# GCM_SCH.net
KiCad netlist of a schematic drawn in Altium Designer
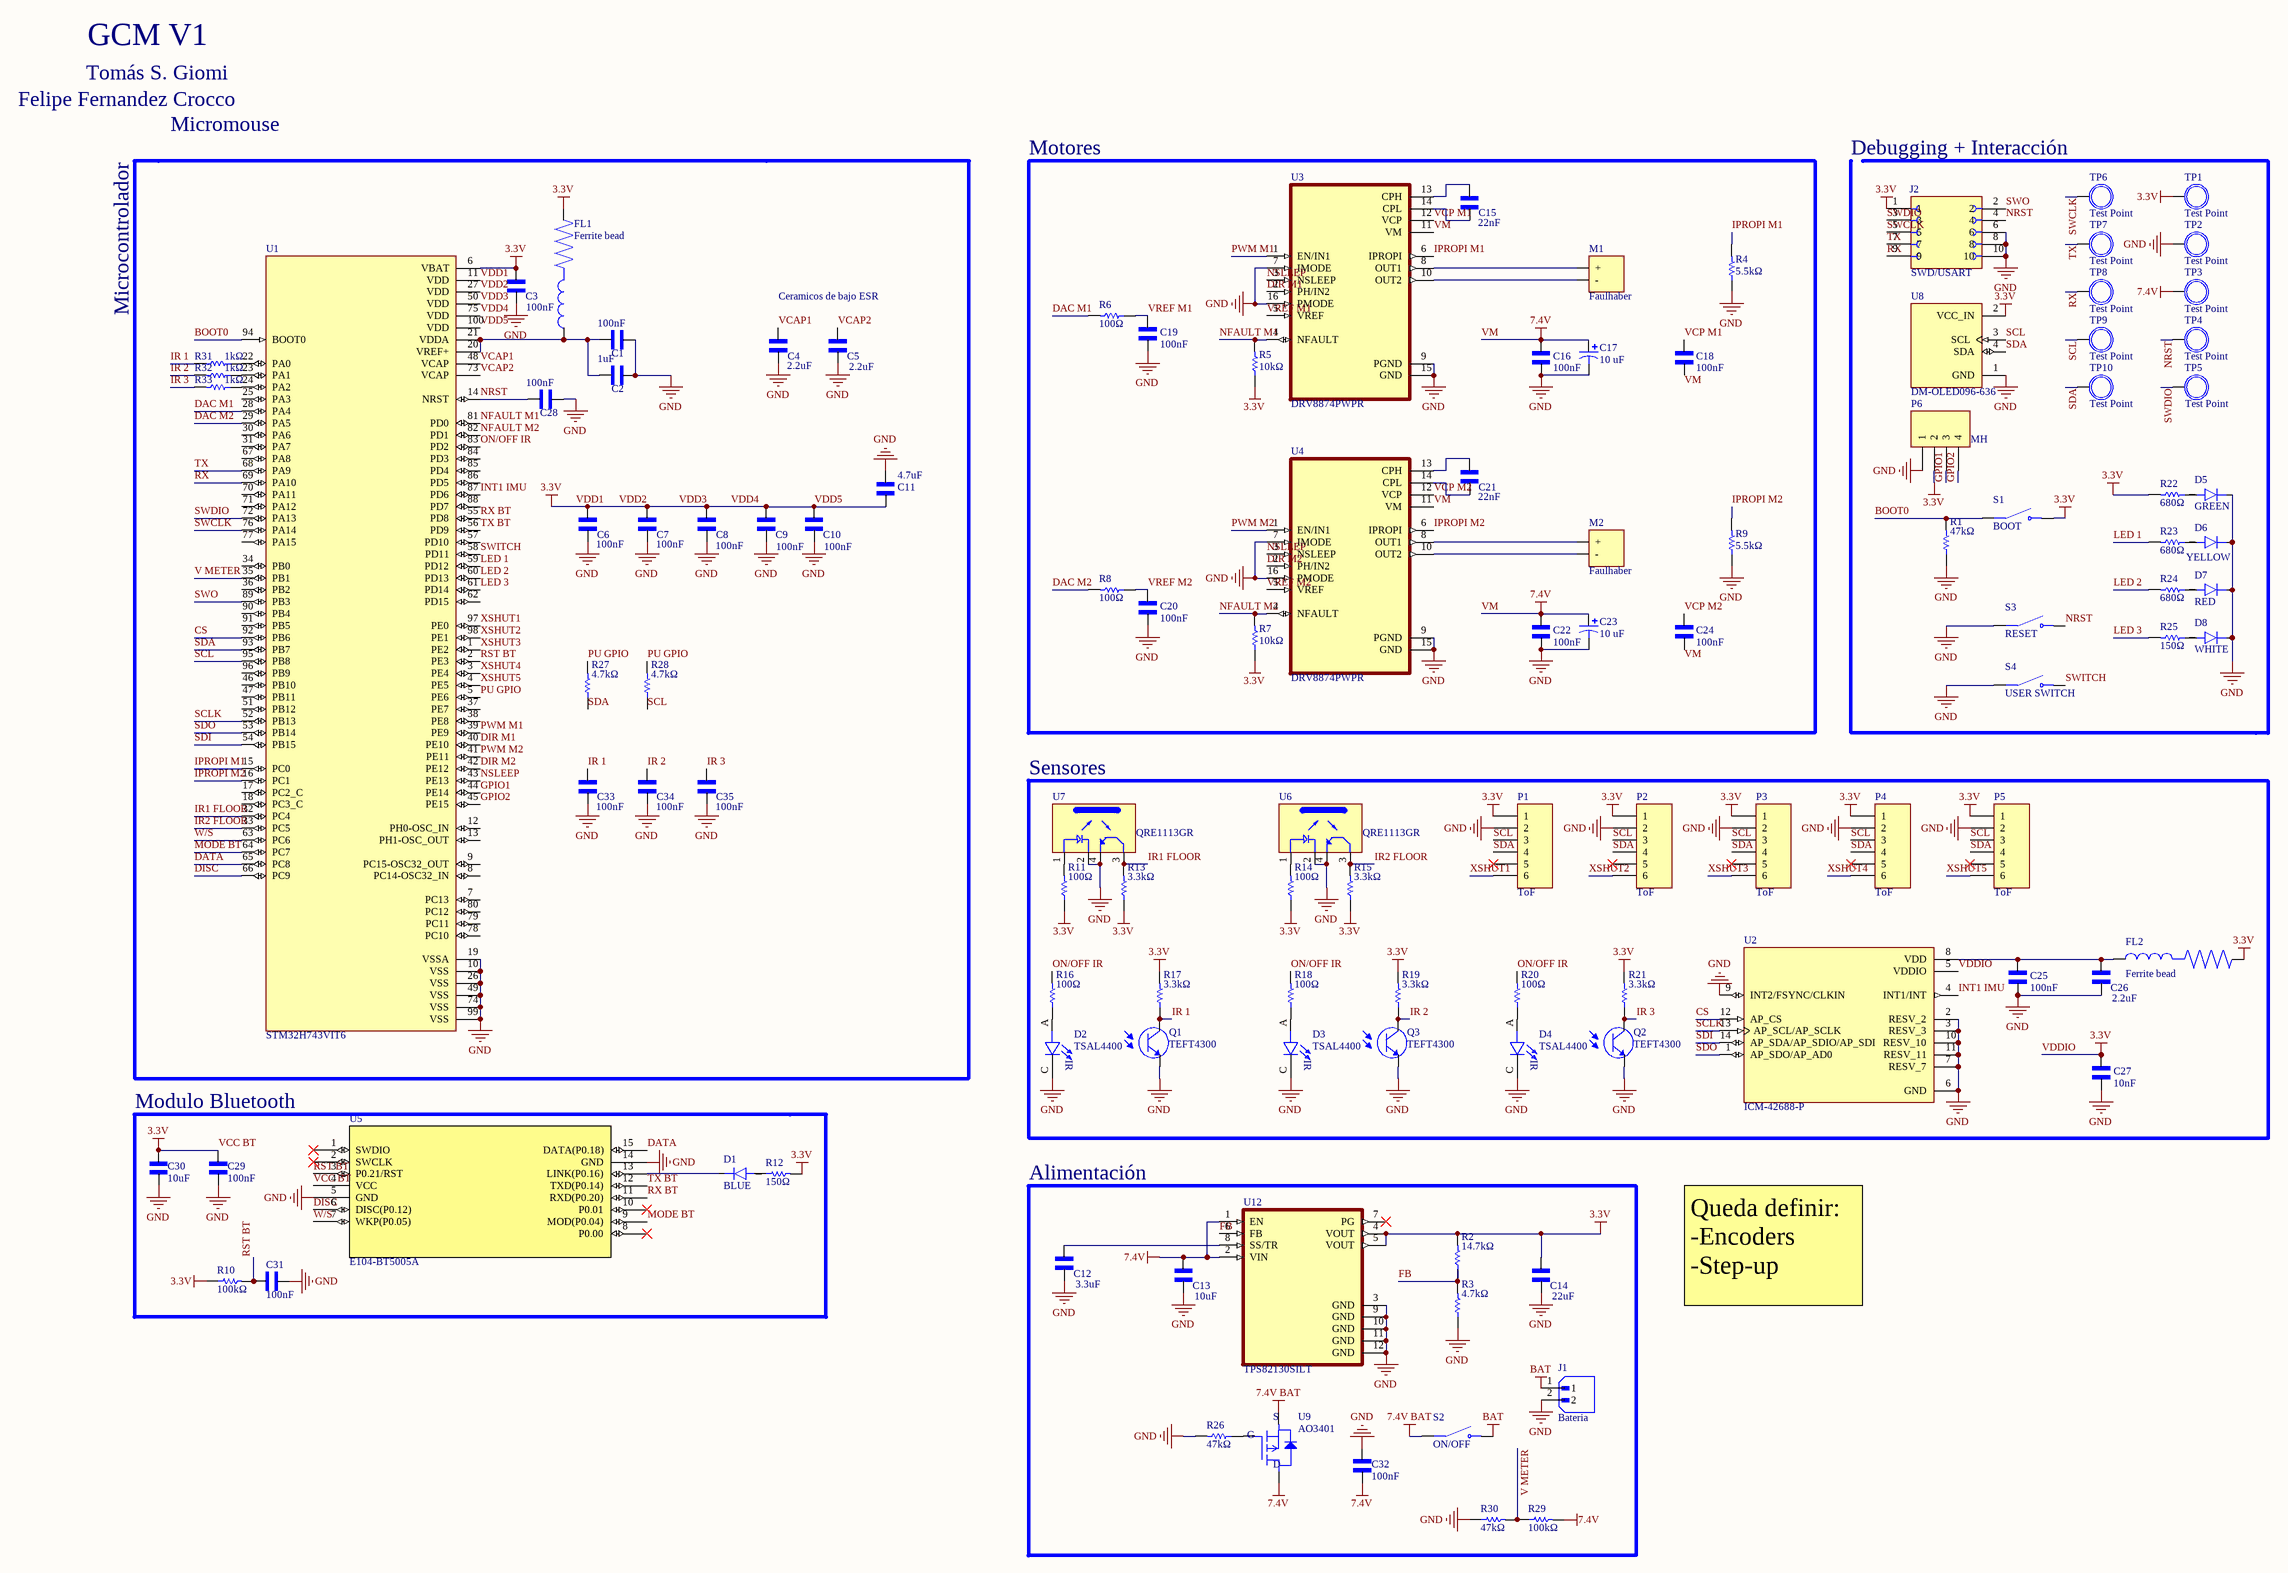
[diagram p0: GCM_SCH.SchDoc]

(export (version "E")
  (design (tool "Eeschema 10.0.6"))
  (components
    (comp (ref "C1")
      (value "100nF")
      (footprint "CAPACITOR TANTALIO")
      (description "0805")
      (fields (field (name "MP") "GRM035R60J475ME15D") (field (name "MF") "Murata"))
      (libsource (lib "") (part "CAPACITOR TANTALIO_1"))
    )
    (comp (ref "C2")
      (value "1uF")
      (footprint "CAPACITOR TANTALIO")
      (description "0805")
      (fields (field (name "MP") "GRM035R60J475ME15D") (field (name "MF") "Murata"))
      (libsource (lib "") (part "CAPACITOR TANTALIO_1"))
    )
    (comp (ref "C3")
      (value "100nF")
      (footprint "CAPACITOR TANTALIO")
      (description "0805")
      (fields (field (name "MP") "GRM035R60J475ME15D") (field (name "MF") "Murata"))
      (libsource (lib "GCMLibreriasSCH") (part "CAPACITOR TANTALIO"))
    )
    (comp (ref "C4")
      (value "2.2uF")
      (footprint "CAPACITOR TANTALIO")
      (description "0805")
      (fields (field (name "MP") "GRM035R60J475ME15D") (field (name "MF") "Murata"))
      (libsource (lib "GCMLibreriasSCH") (part "CAPACITOR TANTALIO"))
    )
    (comp (ref "C5")
      (value "2.2uF")
      (footprint "CAPACITOR TANTALIO")
      (description "0805")
      (fields (field (name "MP") "GRM035R60J475ME15D") (field (name "MF") "Murata"))
      (libsource (lib "GCMLibreriasSCH") (part "CAPACITOR TANTALIO"))
    )
    (comp (ref "C6")
      (value "100nF")
      (footprint "CAPACITOR TANTALIO")
      (description "0805")
      (fields (field (name "MP") "GRM035R60J475ME15D") (field (name "MF") "Murata"))
      (libsource (lib "GCMLibreriasSCH") (part "CAPACITOR TANTALIO"))
    )
    (comp (ref "C7")
      (value "100nF")
      (footprint "CAPACITOR TANTALIO")
      (description "0805")
      (fields (field (name "MP") "GRM035R60J475ME15D") (field (name "MF") "Murata"))
      (libsource (lib "GCMLibreriasSCH") (part "CAPACITOR TANTALIO"))
    )
    (comp (ref "C8")
      (value "100nF")
      (footprint "CAPACITOR TANTALIO")
      (description "0805")
      (fields (field (name "MP") "GRM035R60J475ME15D") (field (name "MF") "Murata"))
      (libsource (lib "GCMLibreriasSCH") (part "CAPACITOR TANTALIO"))
    )
    (comp (ref "C9")
      (value "100nF")
      (footprint "CAPACITOR TANTALIO")
      (description "0805")
      (fields (field (name "MP") "GRM035R60J475ME15D") (field (name "MF") "Murata"))
      (libsource (lib "GCMLibreriasSCH") (part "CAPACITOR TANTALIO"))
    )
    (comp (ref "C10")
      (value "100nF")
      (footprint "CAPACITOR TANTALIO")
      (description "0805")
      (fields (field (name "MP") "GRM035R60J475ME15D") (field (name "MF") "Murata"))
      (libsource (lib "GCMLibreriasSCH") (part "CAPACITOR TANTALIO"))
    )
    (comp (ref "C11")
      (value "4.7uF")
      (footprint "CAPACITOR TANTALIO")
      (description "0805")
      (fields (field (name "MP") "GRM035R60J475ME15D") (field (name "MF") "Murata"))
      (libsource (lib "GCMLibreriasSCH") (part "CAPACITOR TANTALIO"))
    )
    (comp (ref "C12")
      (value "3.3uF")
      (footprint "CAPACITOR TANTALIO")
      (description "0805")
      (fields (field (name "MP") "GRM035R60J475ME15D") (field (name "MF") "Murata"))
      (libsource (lib "GCMLibreriasSCH") (part "CAPACITOR TANTALIO"))
    )
    (comp (ref "C13")
      (value "10uF")
      (footprint "CAPACITOR TANTALIO")
      (description "0805")
      (fields (field (name "MP") "GRM035R60J475ME15D") (field (name "MF") "Murata"))
      (libsource (lib "GCMLibreriasSCH") (part "CAPACITOR TANTALIO"))
    )
    (comp (ref "C14")
      (value "22uF")
      (footprint "CAPACITOR TANTALIO")
      (description "0805")
      (fields (field (name "MP") "GRM035R60J475ME15D") (field (name "MF") "Murata"))
      (libsource (lib "GCMLibreriasSCH") (part "CAPACITOR TANTALIO"))
    )
    (comp (ref "C15")
      (value "22nF")
      (footprint "CAPACITOR TANTALIO")
      (description "0805")
      (fields (field (name "MP") "GRM035R60J475ME15D") (field (name "MF") "Murata"))
      (libsource (lib "GCMLibreriasSCH") (part "CAPACITOR TANTALIO"))
    )
    (comp (ref "C16")
      (value "100nF")
      (footprint "CAPACITOR TANTALIO")
      (description "0805")
      (fields (field (name "MP") "GRM035R60J475ME15D") (field (name "MF") "Murata"))
      (libsource (lib "GCMLibreriasSCH") (part "CAPACITOR TANTALIO"))
    )
    (comp (ref "C17")
      (value "10 uF")
      (footprint "Cap El 10uF")
      (libsource (lib "GCMLibreriasSCH") (part "Cap el 10 uF"))
    )
    (comp (ref "C18")
      (value "100nF")
      (footprint "CAPACITOR TANTALIO")
      (description "0805")
      (fields (field (name "MP") "GRM035R60J475ME15D") (field (name "MF") "Murata"))
      (libsource (lib "GCMLibreriasSCH") (part "CAPACITOR TANTALIO"))
    )
    (comp (ref "C19")
      (value "100nF")
      (footprint "CAPACITOR TANTALIO")
      (description "0805")
      (fields (field (name "MP") "GRM035R60J475ME15D") (field (name "MF") "Murata"))
      (libsource (lib "GCMLibreriasSCH") (part "CAPACITOR TANTALIO"))
    )
    (comp (ref "C20")
      (value "100nF")
      (footprint "CAPACITOR TANTALIO")
      (description "0805")
      (fields (field (name "MP") "GRM035R60J475ME15D") (field (name "MF") "Murata"))
      (libsource (lib "GCMLibreriasSCH") (part "CAPACITOR TANTALIO"))
    )
    (comp (ref "C21")
      (value "22nF")
      (footprint "CAPACITOR TANTALIO")
      (description "0805")
      (fields (field (name "MP") "GRM035R60J475ME15D") (field (name "MF") "Murata"))
      (libsource (lib "GCMLibreriasSCH") (part "CAPACITOR TANTALIO"))
    )
    (comp (ref "C22")
      (value "100nF")
      (footprint "CAPACITOR TANTALIO")
      (description "0805")
      (fields (field (name "MP") "GRM035R60J475ME15D") (field (name "MF") "Murata"))
      (libsource (lib "GCMLibreriasSCH") (part "CAPACITOR TANTALIO"))
    )
    (comp (ref "C23")
      (value "10 uF")
      (footprint "Cap El 10uF")
      (libsource (lib "GCMLibreriasSCH") (part "Cap el 10 uF"))
    )
    (comp (ref "C24")
      (value "100nF")
      (footprint "CAPACITOR TANTALIO")
      (description "0805")
      (fields (field (name "MP") "GRM035R60J475ME15D") (field (name "MF") "Murata"))
      (libsource (lib "GCMLibreriasSCH") (part "CAPACITOR TANTALIO"))
    )
    (comp (ref "C25")
      (value "100nF")
      (footprint "CAPACITOR TANTALIO")
      (description "0805")
      (fields (field (name "MP") "GRM035R60J475ME15D") (field (name "MF") "Murata"))
      (libsource (lib "GCMLibreriasSCH") (part "CAPACITOR TANTALIO"))
    )
    (comp (ref "C26")
      (value "2.2uF")
      (footprint "CAPACITOR TANTALIO")
      (description "0805")
      (fields (field (name "MP") "GRM035R60J475ME15D") (field (name "MF") "Murata"))
      (libsource (lib "GCMLibreriasSCH") (part "CAPACITOR TANTALIO"))
    )
    (comp (ref "C27")
      (value "10nF")
      (footprint "CAPACITOR TANTALIO")
      (description "0805")
      (fields (field (name "MP") "GRM035R60J475ME15D") (field (name "MF") "Murata"))
      (libsource (lib "GCMLibreriasSCH") (part "CAPACITOR TANTALIO"))
    )
    (comp (ref "C28")
      (value "100nF")
      (footprint "CAPACITOR TANTALIO")
      (description "0805")
      (fields (field (name "MP") "GRM035R60J475ME15D") (field (name "MF") "Murata"))
      (libsource (lib "") (part "CAPACITOR TANTALIO_1"))
    )
    (comp (ref "C29")
      (value "100nF")
      (footprint "CAPACITOR TANTALIO")
      (description "0805")
      (fields (field (name "MP") "GRM035R60J475ME15D") (field (name "MF") "Murata"))
      (libsource (lib "GCMLibreriasSCH") (part "CAPACITOR TANTALIO"))
    )
    (comp (ref "C30")
      (value "10uF")
      (footprint "CAPACITOR TANTALIO")
      (description "0805")
      (fields (field (name "MP") "GRM035R60J475ME15D") (field (name "MF") "Murata"))
      (libsource (lib "GCMLibreriasSCH") (part "CAPACITOR TANTALIO"))
    )
    (comp (ref "C31")
      (value "100nF")
      (footprint "CAPACITOR TANTALIO")
      (description "0805")
      (fields (field (name "MP") "GRM035R60J475ME15D") (field (name "MF") "Murata"))
      (libsource (lib "") (part "CAPACITOR TANTALIO_2"))
    )
    (comp (ref "C32")
      (value "100nF")
      (footprint "CAPACITOR TANTALIO")
      (description "0805")
      (fields (field (name "MP") "GRM035R60J475ME15D") (field (name "MF") "Murata"))
      (libsource (lib "") (part "CAPACITOR TANTALIO_3"))
    )
    (comp (ref "C33")
      (value "100nF")
      (footprint "CAPACITOR TANTALIO")
      (description "0805")
      (fields (field (name "MP") "GRM035R60J475ME15D") (field (name "MF") "Murata"))
      (libsource (lib "GCMLibreriasSCH") (part "CAPACITOR TANTALIO"))
    )
    (comp (ref "C34")
      (value "100nF")
      (footprint "CAPACITOR TANTALIO")
      (description "0805")
      (fields (field (name "MP") "GRM035R60J475ME15D") (field (name "MF") "Murata"))
      (libsource (lib "GCMLibreriasSCH") (part "CAPACITOR TANTALIO"))
    )
    (comp (ref "C35")
      (value "100nF")
      (footprint "CAPACITOR TANTALIO")
      (description "0805")
      (fields (field (name "MP") "GRM035R60J475ME15D") (field (name "MF") "Murata"))
      (libsource (lib "GCMLibreriasSCH") (part "CAPACITOR TANTALIO"))
    )
    (comp (ref "D1")
      (value "BLUE")
      (footprint "LED SMD")
      (description "0805")
      (fields (field (name "MP") "597-5311-402F"))
      (libsource (lib "GCMLibreriasSCH") (part "LED SMD"))
    )
    (comp (ref "D2")
      (value "TSAL4400")
      (footprint "GCMLibreriasPCB:LEDRD254W45D335H610")
      (description "Infrared Emitter 940nm 36mW/sr Circular Top Mount 2-Pin T-1 Bulk")
      (fields (field (name "MF") "Vishay Semiconductor"))
      (libsource (lib "GCMLibreriasSCH") (part "TSAL4400"))
    )
    (comp (ref "D3")
      (value "TSAL4400")
      (footprint "GCMLibreriasPCB:LEDRD254W45D335H610")
      (description "Infrared Emitter 940nm 36mW/sr Circular Top Mount 2-Pin T-1 Bulk")
      (fields (field (name "MF") "Vishay Semiconductor"))
      (libsource (lib "GCMLibreriasSCH") (part "TSAL4400"))
    )
    (comp (ref "D4")
      (value "TSAL4400")
      (footprint "GCMLibreriasPCB:LEDRD254W45D335H610")
      (description "Infrared Emitter 940nm 36mW/sr Circular Top Mount 2-Pin T-1 Bulk")
      (fields (field (name "MF") "Vishay Semiconductor"))
      (libsource (lib "GCMLibreriasSCH") (part "TSAL4400"))
    )
    (comp (ref "D5")
      (value "GREEN")
      (footprint "LED SMD")
      (description "0805")
      (fields (field (name "MP") "597-5311-402F"))
      (libsource (lib "GCMLibreriasSCH") (part "LED SMD"))
    )
    (comp (ref "D6")
      (value "YELLOW")
      (footprint "LED SMD")
      (description "0805")
      (fields (field (name "MP") "597-5311-402F"))
      (libsource (lib "GCMLibreriasSCH") (part "LED SMD"))
    )
    (comp (ref "D7")
      (value "RED")
      (footprint "LED SMD")
      (description "0805")
      (fields (field (name "MP") "597-5311-402F"))
      (libsource (lib "GCMLibreriasSCH") (part "LED SMD"))
    )
    (comp (ref "D8")
      (value "WHITE")
      (footprint "LED SMD")
      (description "0805")
      (fields (field (name "MP") "597-5311-402F"))
      (libsource (lib "GCMLibreriasSCH") (part "LED SMD"))
    )
    (comp (ref "FL1")
      (value "Ferrite bead")
      (footprint "BEADC1608X95N")
      (description "600 Ohms @ 100 MHz 1 - Ferrite Bead 0603 (1608 Metric) 500mA 380mOhm")
      (fields (field (name "MF") "Murata") (field (name "MP") "BLM18AG601SN1D"))
      (libsource (lib "GCMLibreriasSCH") (part "BLM18AG601SN1D"))
    )
    (comp (ref "FL2")
      (value "Ferrite bead")
      (footprint "BEADC1608X95N")
      (description "600 Ohms @ 100 MHz 1 - Ferrite Bead 0603 (1608 Metric) 500mA 380mOhm")
      (fields (field (name "MF") "Murata") (field (name "MP") "BLM18AG601SN1D"))
      (libsource (lib "GCMLibreriasSCH") (part "BLM18AG601SN1D"))
    )
    (comp (ref "J1")
      (value "Bateria")
      (footprint "JST_B2B-XH-A")
      (fields
        (field (name "MF") "{'manufacturer': u'JST Sales America Inc.'}")
        (field (name "MP") "B2B-XH-A")
      )
      (libsource (lib "GCMLibreriasSCH") (part "B2B-XH-A"))
    )
    (comp (ref "J2")
      (value "SWD/USART")
      (footprint "AMPHENOL_20021311-00026T4LF")
      (fields (field (name "MF") "Amphenol ICC") (field (name "MP") "20021311-00026T4LF"))
      (libsource (lib "GCMLibreriasSCH") (part "20021311-00026T4LF"))
    )
    (comp (ref "M1")
      (value "Faulhaber")
      (footprint "MOTOR")
      (fields (field (name "PUBLISHER") "Altium Limited"))
      (libsource (lib "GCMLibreriasSCH") (part "Faulhaber"))
    )
    (comp (ref "M2")
      (value "Faulhaber")
      (footprint "MOTOR")
      (fields (field (name "PUBLISHER") "Altium Limited"))
      (libsource (lib "GCMLibreriasSCH") (part "Faulhaber"))
    )
    (comp (ref "P1")
      (value "ToF")
      (footprint "FHDR1X6")
      (fields (field (name "PUBLISHER") "Altium Limited"))
      (libsource (lib "GCMLibreriasSCH") (part "FHeader 6X1"))
    )
    (comp (ref "P2")
      (value "ToF")
      (footprint "FHDR1X6")
      (fields (field (name "PUBLISHER") "Altium Limited"))
      (libsource (lib "GCMLibreriasSCH") (part "FHeader 6X1"))
    )
    (comp (ref "P3")
      (value "ToF")
      (footprint "FHDR1X6")
      (fields (field (name "PUBLISHER") "Altium Limited"))
      (libsource (lib "GCMLibreriasSCH") (part "FHeader 6X1"))
    )
    (comp (ref "P4")
      (value "ToF")
      (footprint "FHDR1X6")
      (fields (field (name "PUBLISHER") "Altium Limited"))
      (libsource (lib "GCMLibreriasSCH") (part "FHeader 6X1"))
    )
    (comp (ref "P5")
      (value "ToF")
      (footprint "FHDR1X6")
      (fields (field (name "PUBLISHER") "Altium Limited"))
      (libsource (lib "GCMLibreriasSCH") (part "FHeader 6X1"))
    )
    (comp (ref "P6")
      (value "MH")
      (footprint "FHDR1X4")
      (fields (field (name "PUBLISHER") "Altium Limited"))
      (libsource (lib "GCMLibreriasSCH") (part "FHeader 4X1_1"))
    )
    (comp (ref "Q1")
      (value "TEFT4300")
      (footprint "XDCR_TEFT4300")
      (description "Phototransistors 925nm Top View Radial, 3mm Dia (T-1)")
      (fields (field (name "MF") "Vishay Semiconductor"))
      (libsource (lib "GCMLibreriasSCH") (part "TEFT4300"))
    )
    (comp (ref "Q2")
      (value "TEFT4300")
      (footprint "XDCR_TEFT4300")
      (description "Phototransistors 925nm Top View Radial, 3mm Dia (T-1)")
      (fields (field (name "MF") "Vishay Semiconductor"))
      (libsource (lib "GCMLibreriasSCH") (part "TEFT4300"))
    )
    (comp (ref "Q3")
      (value "TEFT4300")
      (footprint "XDCR_TEFT4300")
      (description "Phototransistors 925nm Top View Radial, 3mm Dia (T-1)")
      (fields (field (name "MF") "Vishay Semiconductor"))
      (libsource (lib "GCMLibreriasSCH") (part "TEFT4300"))
    )
    (comp (ref "R1")
      (value "47kΩ")
      (footprint "RESISTENCIA SMD")
      (description "0805")
      (fields (field (name "PUBLISHER") "Altium Limited"))
      (libsource (lib "GCMLibreriasSCH") (part "RESISTENCIA"))
    )
    (comp (ref "R2")
      (value "14.7kΩ")
      (footprint "RESISTENCIA SMD")
      (description "0805")
      (fields (field (name "PUBLISHER") "Altium Limited"))
      (libsource (lib "GCMLibreriasSCH") (part "RESISTENCIA"))
    )
    (comp (ref "R3")
      (value "4.7kΩ")
      (footprint "RESISTENCIA SMD")
      (description "0805")
      (fields (field (name "PUBLISHER") "Altium Limited"))
      (libsource (lib "GCMLibreriasSCH") (part "RESISTENCIA"))
    )
    (comp (ref "R4")
      (value "5.5kΩ")
      (footprint "RESISTENCIA SMD")
      (description "0805")
      (fields (field (name "PUBLISHER") "Altium Limited"))
      (libsource (lib "GCMLibreriasSCH") (part "RESISTENCIA"))
    )
    (comp (ref "R5")
      (value "10kΩ")
      (footprint "RESISTENCIA SMD")
      (description "0805")
      (fields (field (name "PUBLISHER") "Altium Limited"))
      (libsource (lib "GCMLibreriasSCH") (part "RESISTENCIA"))
    )
    (comp (ref "R6")
      (value "100Ω")
      (footprint "RESISTENCIA SMD")
      (description "0805")
      (fields (field (name "PUBLISHER") "Altium Limited"))
      (libsource (lib "GCMLibreriasSCH") (part "RESISTENCIA"))
    )
    (comp (ref "R7")
      (value "10kΩ")
      (footprint "RESISTENCIA SMD")
      (description "0805")
      (fields (field (name "PUBLISHER") "Altium Limited"))
      (libsource (lib "GCMLibreriasSCH") (part "RESISTENCIA"))
    )
    (comp (ref "R8")
      (value "100Ω")
      (footprint "RESISTENCIA SMD")
      (description "0805")
      (fields (field (name "PUBLISHER") "Altium Limited"))
      (libsource (lib "GCMLibreriasSCH") (part "RESISTENCIA"))
    )
    (comp (ref "R9")
      (value "5.5kΩ")
      (footprint "RESISTENCIA SMD")
      (description "0805")
      (fields (field (name "PUBLISHER") "Altium Limited"))
      (libsource (lib "GCMLibreriasSCH") (part "RESISTENCIA"))
    )
    (comp (ref "R10")
      (value "100kΩ")
      (footprint "RESISTENCIA SMD")
      (description "0805")
      (fields (field (name "PUBLISHER") "Altium Limited"))
      (libsource (lib "GCMLibreriasSCH") (part "RESISTENCIA"))
    )
    (comp (ref "R11")
      (value "100Ω")
      (footprint "RESISTENCIA SMD")
      (description "0805")
      (fields (field (name "PUBLISHER") "Altium Limited"))
      (libsource (lib "GCMLibreriasSCH") (part "RESISTENCIA"))
    )
    (comp (ref "R12")
      (value "150Ω")
      (footprint "RESISTENCIA SMD")
      (description "0805")
      (fields (field (name "PUBLISHER") "Altium Limited"))
      (libsource (lib "GCMLibreriasSCH") (part "RESISTENCIA"))
    )
    (comp (ref "R13")
      (value "3.3kΩ")
      (footprint "RESISTENCIA SMD")
      (description "0805")
      (fields (field (name "PUBLISHER") "Altium Limited"))
      (libsource (lib "GCMLibreriasSCH") (part "RESISTENCIA"))
    )
    (comp (ref "R14")
      (value "100Ω")
      (footprint "RESISTENCIA SMD")
      (description "0805")
      (fields (field (name "PUBLISHER") "Altium Limited"))
      (libsource (lib "GCMLibreriasSCH") (part "RESISTENCIA"))
    )
    (comp (ref "R15")
      (value "3.3kΩ")
      (footprint "RESISTENCIA SMD")
      (description "0805")
      (fields (field (name "PUBLISHER") "Altium Limited"))
      (libsource (lib "GCMLibreriasSCH") (part "RESISTENCIA"))
    )
    (comp (ref "R16")
      (value "100Ω")
      (footprint "RESISTENCIA SMD")
      (description "0805")
      (fields (field (name "PUBLISHER") "Altium Limited"))
      (libsource (lib "GCMLibreriasSCH") (part "RESISTENCIA"))
    )
    (comp (ref "R17")
      (value "3.3kΩ")
      (footprint "RESISTENCIA SMD")
      (description "0805")
      (fields (field (name "PUBLISHER") "Altium Limited"))
      (libsource (lib "GCMLibreriasSCH") (part "RESISTENCIA"))
    )
    (comp (ref "R18")
      (value "100Ω")
      (footprint "RESISTENCIA SMD")
      (description "0805")
      (fields (field (name "PUBLISHER") "Altium Limited"))
      (libsource (lib "GCMLibreriasSCH") (part "RESISTENCIA"))
    )
    (comp (ref "R19")
      (value "3.3kΩ")
      (footprint "RESISTENCIA SMD")
      (description "0805")
      (fields (field (name "PUBLISHER") "Altium Limited"))
      (libsource (lib "GCMLibreriasSCH") (part "RESISTENCIA"))
    )
    (comp (ref "R20")
      (value "100Ω")
      (footprint "RESISTENCIA SMD")
      (description "0805")
      (fields (field (name "PUBLISHER") "Altium Limited"))
      (libsource (lib "GCMLibreriasSCH") (part "RESISTENCIA"))
    )
    (comp (ref "R21")
      (value "3.3kΩ")
      (footprint "RESISTENCIA SMD")
      (description "0805")
      (fields (field (name "PUBLISHER") "Altium Limited"))
      (libsource (lib "GCMLibreriasSCH") (part "RESISTENCIA"))
    )
    (comp (ref "R22")
      (value "680Ω")
      (footprint "RESISTENCIA SMD")
      (description "0805")
      (fields (field (name "PUBLISHER") "Altium Limited"))
      (libsource (lib "GCMLibreriasSCH") (part "RESISTENCIA"))
    )
    (comp (ref "R23")
      (value "680Ω")
      (footprint "RESISTENCIA SMD")
      (description "0805")
      (fields (field (name "PUBLISHER") "Altium Limited"))
      (libsource (lib "GCMLibreriasSCH") (part "RESISTENCIA"))
    )
    (comp (ref "R24")
      (value "680Ω")
      (footprint "RESISTENCIA SMD")
      (description "0805")
      (fields (field (name "PUBLISHER") "Altium Limited"))
      (libsource (lib "GCMLibreriasSCH") (part "RESISTENCIA"))
    )
    (comp (ref "R25")
      (value "150Ω")
      (footprint "RESISTENCIA SMD")
      (description "0805")
      (fields (field (name "PUBLISHER") "Altium Limited"))
      (libsource (lib "GCMLibreriasSCH") (part "RESISTENCIA"))
    )
    (comp (ref "R26")
      (value "47kΩ")
      (footprint "RESISTENCIA SMD")
      (description "0805")
      (fields (field (name "PUBLISHER") "Altium Limited"))
      (libsource (lib "GCMLibreriasSCH") (part "RESISTENCIA"))
    )
    (comp (ref "R27")
      (value "4.7kΩ")
      (footprint "RESISTENCIA SMD")
      (description "0805")
      (fields (field (name "PUBLISHER") "Altium Limited"))
      (libsource (lib "GCMLibreriasSCH") (part "RESISTENCIA"))
    )
    (comp (ref "R28")
      (value "4.7kΩ")
      (footprint "RESISTENCIA SMD")
      (description "0805")
      (fields (field (name "PUBLISHER") "Altium Limited"))
      (libsource (lib "GCMLibreriasSCH") (part "RESISTENCIA"))
    )
    (comp (ref "R29")
      (value "100kΩ")
      (footprint "RESISTENCIA SMD")
      (description "0805")
      (fields (field (name "PUBLISHER") "Altium Limited"))
      (libsource (lib "GCMLibreriasSCH") (part "RESISTENCIA"))
    )
    (comp (ref "R30")
      (value "47kΩ")
      (footprint "RESISTENCIA SMD")
      (description "0805")
      (fields (field (name "PUBLISHER") "Altium Limited"))
      (libsource (lib "GCMLibreriasSCH") (part "RESISTENCIA"))
    )
    (comp (ref "R31")
      (value "1kΩ")
      (footprint "RESISTENCIA SMD")
      (description "0805")
      (fields (field (name "PUBLISHER") "Altium Limited"))
      (libsource (lib "GCMLibreriasSCH") (part "RESISTENCIA"))
    )
    (comp (ref "R32")
      (value "1kΩ")
      (footprint "RESISTENCIA SMD")
      (description "0805")
      (fields (field (name "PUBLISHER") "Altium Limited"))
      (libsource (lib "GCMLibreriasSCH") (part "RESISTENCIA"))
    )
    (comp (ref "R33")
      (value "1kΩ")
      (footprint "RESISTENCIA SMD")
      (description "0805")
      (fields (field (name "PUBLISHER") "Altium Limited"))
      (libsource (lib "GCMLibreriasSCH") (part "RESISTENCIA"))
    )
    (comp (ref "S1")
      (value "BOOT")
      (footprint "SW_TS09-63-25-WT-160-SMT-TR")
      (description "6.1 x 3.7 mm, 2.5 mm Actuator Height, 160 gf, White, Surface Mount, SPST, Tactile Switch")
      (fields (field (name "MF") "Same Sky") (field (name "MP") "TS09-63-25-WT-160-SMT-TR"))
      (libsource (lib "GCMLibreriasSCH") (part "TS09-63-25-WT-160-SMT-TR"))
    )
    (comp (ref "S2")
      (value "ON/OFF")
      (footprint "SW_L101011ML04Q")
      (description "Switch Slide ON OFF SPST Side Slide 4A 250VAC 125VDC PC Pins Thru-Hole Bulk")
      (fields (field (name "MF") "C&K") (field (name "MP") "L101011ML04Q"))
      (libsource (lib "GCMLibreriasSCH") (part "L101011ML04Q"))
    )
    (comp (ref "S3")
      (value "RESET")
      (footprint "SW_TS09-63-25-WT-160-SMT-TR")
      (description "6.1 x 3.7 mm, 2.5 mm Actuator Height, 160 gf, White, Surface Mount, SPST, Tactile Switch")
      (fields (field (name "MF") "Same Sky") (field (name "MP") "TS09-63-25-WT-160-SMT-TR"))
      (libsource (lib "GCMLibreriasSCH") (part "TS09-63-25-WT-160-SMT-TR"))
    )
    (comp (ref "S4")
      (value "USER SWITCH")
      (footprint "SW_TS09-63-25-WT-160-SMT-TR")
      (description "6.1 x 3.7 mm, 2.5 mm Actuator Height, 160 gf, White, Surface Mount, SPST, Tactile Switch")
      (fields (field (name "MF") "Same Sky") (field (name "MP") "TS09-63-25-WT-160-SMT-TR"))
      (libsource (lib "GCMLibreriasSCH") (part "TS09-63-25-WT-160-SMT-TR"))
    )
    (comp (ref "TP1")
      (value "Test Point")
      (footprint "TestPoint")
      (libsource (lib "GCMLibreriasSCH") (part "Test Point"))
    )
    (comp (ref "TP2")
      (value "Test Point")
      (footprint "TestPoint")
      (libsource (lib "GCMLibreriasSCH") (part "Test Point"))
    )
    (comp (ref "TP3")
      (value "Test Point")
      (footprint "TestPoint")
      (libsource (lib "GCMLibreriasSCH") (part "Test Point"))
    )
    (comp (ref "TP4")
      (value "Test Point")
      (footprint "TestPoint")
      (libsource (lib "GCMLibreriasSCH") (part "Test Point"))
    )
    (comp (ref "TP5")
      (value "Test Point")
      (footprint "TestPoint")
      (libsource (lib "GCMLibreriasSCH") (part "Test Point"))
    )
    (comp (ref "TP6")
      (value "Test Point")
      (footprint "TestPoint")
      (libsource (lib "GCMLibreriasSCH") (part "Test Point"))
    )
    (comp (ref "TP7")
      (value "Test Point")
      (footprint "TestPoint")
      (libsource (lib "GCMLibreriasSCH") (part "Test Point"))
    )
    (comp (ref "TP8")
      (value "Test Point")
      (footprint "TestPoint")
      (libsource (lib "GCMLibreriasSCH") (part "Test Point"))
    )
    (comp (ref "TP9")
      (value "Test Point")
      (footprint "TestPoint")
      (libsource (lib "GCMLibreriasSCH") (part "Test Point"))
    )
    (comp (ref "TP10")
      (value "Test Point")
      (footprint "TestPoint")
      (libsource (lib "GCMLibreriasSCH") (part "Test Point"))
    )
    (comp (ref "U1")
      (value "STM32H743VIT6")
      (footprint "QFP50P1600X1600X160-100N")
      (fields (field (name "MF") "STMicroelectronics"))
      (libsource (lib "GCMLibreriasSCH") (part "STM32H743VIT6"))
    )
    (comp (ref "U2")
      (value "ICM-42688-P")
      (footprint "GCMLibreriasPCB:PQFN50P300X250X97-14N")
      (description "Accelerometer, Gyroscope, 6 Axis Sensor Output")
      (libsource (lib "GCMLibreriasSCH") (part "ICM-42688-P"))
    )
    (comp (ref "U3")
      (value "DRV8874PWPR")
      (footprint "SOP65P640X120-17N")
      (description "40-V, 6-A H-bridge motor driver with integrated current sensing feedback")
      (fields (field (name "MF") "Texas Instruments"))
      (libsource (lib "GCMLibreriasSCH") (part "DRV8874PWPR"))
    )
    (comp (ref "U4")
      (value "DRV8874PWPR")
      (footprint "SOP65P640X120-17N")
      (description "40-V, 6-A H-bridge motor driver with integrated current sensing feedback")
      (fields (field (name "MF") "Texas Instruments"))
      (libsource (lib "GCMLibreriasSCH") (part "DRV8874PWPR"))
    )
    (comp (ref "U5")
      (value "E104-BT5005A")
      (footprint "MOD15_E104-BT5005A_BYT")
      (description "No Description Available")
      (fields (field (name "COPYRIGHT") "Copyright (C) 2026 Ultra Librarian. All rights reserved."))
      (libsource (lib "GCMLibreriasSCH") (part "E104-BT5005A"))
    )
    (comp (ref "U6")
      (value "QRE1113GR")
      (footprint "SOIC180P460X187-4N")
      (description "Reflective Optical Sensor 0.039 (1mm) 4-SMD, Gull Wing")
      (fields (field (name "MF") "ON Semiconductor"))
      (libsource (lib "GCMLibreriasSCH") (part "QRE1113GR"))
    )
    (comp (ref "U7")
      (value "QRE1113GR")
      (footprint "SOIC180P460X187-4N")
      (description "Reflective Optical Sensor 0.039 (1mm) 4-SMD, Gull Wing")
      (fields (field (name "MF") "ON Semiconductor"))
      (libsource (lib "GCMLibreriasSCH") (part "QRE1113GR"))
    )
    (comp (ref "U8")
      (value "DM-OLED096-636")
      (footprint "MODULE_DM-OLED096-636")
      (description "0.96â€ 128 X 64 MONOCHROME GRAPHIC OLED DISPLAY MODULE - I2C")
      (fields (field (name "MF") "Display Module"))
      (libsource (lib "GCMLibreriasSCH") (part "DM-OLED096-636"))
    )
    (comp (ref "U9")
      (value "AO3401")
      (footprint "SOT23")
      (description "P-Channel 30 V 4A (Ta) 1.4W (Ta) Surface Mount SOT-23-3")
      (fields (field (name "MF") "Alpha & Omega Semiconductor"))
      (libsource (lib "GCMLibreriasSCH") (part "AO3401"))
    )
    (comp (ref "U12")
      (value "TPS82130SILT")
      (footprint "CONV_TPS82140SILR")
      (description "Non-Isolated PoL Module DC DC Converter 1 Output 0.9 ~ 5V - - - 3A 3V - 17V Input")
      (fields (field (name "MF") "Texas Instruments") (field (name "MP") "TPS82130SIL"))
      (libsource (lib "GCMLibreriasSCH") (part "TPS82130SILT"))
    )
  )
  (nets
    (net (code "1") (name "/BOOT0") (class "Default")
      (node (ref "R1") (pin "2") (pinfunction "2_2") (pintype "passive"))
      (node (ref "S1") (pin "1") (pinfunction "1_1") (pintype "passive"))
      (node (ref "U1") (pin "94") (pinfunction "BOOT0_94") (pintype "input"))
    )
    (net (code "2") (name "/CS") (class "Default")
      (node (ref "U1") (pin "92") (pinfunction "PB6_92") (pintype "bidirectional"))
      (node (ref "U2") (pin "12") (pinfunction "AP_CS_12") (pintype "input"))
    )
    (net (code "3") (name "/DAC M1") (class "Default")
      (node (ref "R6") (pin "2") (pinfunction "2_2") (pintype "passive"))
      (node (ref "U1") (pin "28") (pinfunction "PA4_28") (pintype "bidirectional"))
    )
    (net (code "4") (name "/DAC M2") (class "Default")
      (node (ref "R8") (pin "2") (pinfunction "2_2") (pintype "passive"))
      (node (ref "U1") (pin "29") (pinfunction "PA5_29") (pintype "bidirectional"))
    )
    (net (code "5") (name "/DATA") (class "Default")
      (node (ref "U1") (pin "65") (pinfunction "PC8_65") (pintype "bidirectional"))
      (node (ref "U5") (pin "15") (pinfunction "DATA(P0.18)_15") (pintype "bidirectional"))
    )
    (net (code "6") (name "/DIR M1") (class "Default")
      (node (ref "U1") (pin "40") (pinfunction "PE10_40") (pintype "bidirectional"))
      (node (ref "U3") (pin "2") (pinfunction "PH/IN2_2") (pintype "input"))
    )
    (net (code "7") (name "/DIR M2") (class "Default")
      (node (ref "U1") (pin "42") (pinfunction "PE12_42") (pintype "bidirectional"))
      (node (ref "U4") (pin "2") (pinfunction "PH/IN2_2") (pintype "input"))
    )
    (net (code "8") (name "/DISC") (class "Default")
      (node (ref "U1") (pin "66") (pinfunction "PC9_66") (pintype "bidirectional"))
      (node (ref "U5") (pin "6") (pinfunction "DISC(P0.12)_6") (pintype "bidirectional"))
    )
    (net (code "9") (name "/FB") (class "Default")
      (node (ref "R2") (pin "1") (pinfunction "1_1") (pintype "passive"))
      (node (ref "R3") (pin "2") (pinfunction "2_2") (pintype "passive"))
      (node (ref "U12") (pin "6") (pinfunction "FB_6") (pintype "input"))
    )
    (net (code "10") (name "/GPIO1") (class "Default")
      (node (ref "P6") (pin "3") (pinfunction "3_3") (pintype "passive"))
      (node (ref "U1") (pin "44") (pinfunction "PE14_44") (pintype "bidirectional"))
    )
    (net (code "11") (name "/GPIO2") (class "Default")
      (node (ref "P6") (pin "4") (pinfunction "4_4") (pintype "passive"))
      (node (ref "U1") (pin "45") (pinfunction "PE15_45") (pintype "bidirectional"))
    )
    (net (code "12") (name "/INT1 IMU") (class "Default")
      (node (ref "U1") (pin "87") (pinfunction "PD6_87") (pintype "bidirectional"))
      (node (ref "U2") (pin "4") (pinfunction "INT1/INT_4") (pintype "output"))
    )
    (net (code "13") (name "/IPROPI M1") (class "Default")
      (node (ref "R4") (pin "2") (pinfunction "2_2") (pintype "passive"))
      (node (ref "U1") (pin "15") (pinfunction "PC0_15") (pintype "bidirectional"))
      (node (ref "U3") (pin "6") (pinfunction "IPROPI_6") (pintype "output"))
    )
    (net (code "14") (name "/IPROPI M2") (class "Default")
      (node (ref "R9") (pin "2") (pinfunction "2_2") (pintype "passive"))
      (node (ref "U1") (pin "16") (pinfunction "PC1_16") (pintype "bidirectional"))
      (node (ref "U4") (pin "6") (pinfunction "IPROPI_6") (pintype "output"))
    )
    (net (code "15") (name "/IR 1") (class "Default")
      (node (ref "C33") (pin "2") (pinfunction "2_2") (pintype "passive"))
      (node (ref "Q1") (pin "C") (pinfunction "C_C") (pintype "passive"))
      (node (ref "R17") (pin "1") (pinfunction "1_1") (pintype "passive"))
      (node (ref "R31") (pin "2") (pinfunction "2_2") (pintype "passive"))
    )
    (net (code "16") (name "/IR 2") (class "Default")
      (node (ref "C34") (pin "2") (pinfunction "2_2") (pintype "passive"))
      (node (ref "Q3") (pin "C") (pinfunction "C_C") (pintype "passive"))
      (node (ref "R19") (pin "1") (pinfunction "1_1") (pintype "passive"))
      (node (ref "R32") (pin "2") (pinfunction "2_2") (pintype "passive"))
    )
    (net (code "17") (name "/IR 3") (class "Default")
      (node (ref "C35") (pin "2") (pinfunction "2_2") (pintype "passive"))
      (node (ref "Q2") (pin "C") (pinfunction "C_C") (pintype "passive"))
      (node (ref "R21") (pin "1") (pinfunction "1_1") (pintype "passive"))
      (node (ref "R33") (pin "2") (pinfunction "2_2") (pintype "passive"))
    )
    (net (code "18") (name "/IR1 FLOOR") (class "Default")
      (node (ref "R13") (pin "2") (pinfunction "2_2") (pintype "passive"))
      (node (ref "U1") (pin "32") (pinfunction "PC4_32") (pintype "bidirectional"))
      (node (ref "U7") (pin "3") (pinfunction "CT_3") (pintype "passive"))
    )
    (net (code "19") (name "/IR2 FLOOR") (class "Default")
      (node (ref "R15") (pin "2") (pinfunction "2_2") (pintype "passive"))
      (node (ref "U1") (pin "33") (pinfunction "PC5_33") (pintype "bidirectional"))
      (node (ref "U6") (pin "3") (pinfunction "CT_3") (pintype "passive"))
    )
    (net (code "20") (name "/LED 1") (class "Default")
      (node (ref "R23") (pin "2") (pinfunction "2_2") (pintype "passive"))
      (node (ref "U1") (pin "59") (pinfunction "PD12_59") (pintype "bidirectional"))
    )
    (net (code "21") (name "/LED 2") (class "Default")
      (node (ref "R24") (pin "2") (pinfunction "2_2") (pintype "passive"))
      (node (ref "U1") (pin "60") (pinfunction "PD13_60") (pintype "bidirectional"))
    )
    (net (code "22") (name "/LED 3") (class "Default")
      (node (ref "R25") (pin "2") (pinfunction "2_2") (pintype "passive"))
      (node (ref "U1") (pin "61") (pinfunction "PD14_61") (pintype "bidirectional"))
    )
    (net (code "23") (name "/MODE BT") (class "Default")
      (node (ref "U1") (pin "64") (pinfunction "PC7_64") (pintype "bidirectional"))
      (node (ref "U5") (pin "9") (pinfunction "MOD(P0.04)_9") (pintype "bidirectional"))
    )
    (net (code "24") (name "/NFAULT M1") (class "Default")
      (node (ref "R5") (pin "2") (pinfunction "2_2") (pintype "passive"))
      (node (ref "U1") (pin "81") (pinfunction "PD0_81") (pintype "bidirectional"))
      (node (ref "U3") (pin "4") (pinfunction "NFAULT_4") (pintype "bidirectional"))
    )
    (net (code "25") (name "/NFAULT M2") (class "Default")
      (node (ref "R7") (pin "2") (pinfunction "2_2") (pintype "passive"))
      (node (ref "U1") (pin "82") (pinfunction "PD1_82") (pintype "bidirectional"))
      (node (ref "U4") (pin "4") (pinfunction "NFAULT_4") (pintype "bidirectional"))
    )
    (net (code "26") (name "/NRST") (class "Default")
      (node (ref "C28") (pin "1") (pinfunction "1_1") (pintype "passive"))
      (node (ref "J2") (pin "4") (pinfunction "4_4") (pintype "passive"))
      (node (ref "S3") (pin "2") (pinfunction "2_2") (pintype "passive"))
      (node (ref "TP4") (pin "1") (pinfunction "1_1") (pintype "passive"))
      (node (ref "U1") (pin "14") (pinfunction "NRST_14") (pintype "bidirectional"))
    )
    (net (code "27") (name "/NSLEEP") (class "Default")
      (node (ref "U1") (pin "43") (pinfunction "PE13_43") (pintype "bidirectional"))
      (node (ref "U3") (pin "3") (pinfunction "NSLEEP_3") (pintype "input"))
      (node (ref "U4") (pin "3") (pinfunction "NSLEEP_3") (pintype "input"))
    )
    (net (code "28") (name "/ON{slash}OFF IR") (class "Default")
      (node (ref "R16") (pin "2") (pinfunction "2_2") (pintype "passive"))
      (node (ref "R18") (pin "2") (pinfunction "2_2") (pintype "passive"))
      (node (ref "R20") (pin "2") (pinfunction "2_2") (pintype "passive"))
      (node (ref "U1") (pin "83") (pinfunction "PD2_83") (pintype "bidirectional"))
    )
    (net (code "29") (name "/PU GPIO") (class "Default")
      (node (ref "R27") (pin "2") (pinfunction "2_2") (pintype "passive"))
      (node (ref "R28") (pin "2") (pinfunction "2_2") (pintype "passive"))
      (node (ref "U1") (pin "5") (pinfunction "PE6_5") (pintype "bidirectional"))
    )
    (net (code "30") (name "/PWM M1") (class "Default")
      (node (ref "U1") (pin "39") (pinfunction "PE9_39") (pintype "bidirectional"))
      (node (ref "U3") (pin "1") (pinfunction "EN/IN1_1") (pintype "input"))
    )
    (net (code "31") (name "/PWM M2") (class "Default")
      (node (ref "U1") (pin "41") (pinfunction "PE11_41") (pintype "bidirectional"))
      (node (ref "U4") (pin "1") (pinfunction "EN/IN1_1") (pintype "input"))
    )
    (net (code "32") (name "/RST BT") (class "Default")
      (node (ref "C31") (pin "2") (pinfunction "2_2") (pintype "passive"))
      (node (ref "R10") (pin "2") (pinfunction "2_2") (pintype "passive"))
      (node (ref "U1") (pin "2") (pinfunction "PE3_2") (pintype "bidirectional"))
      (node (ref "U5") (pin "3") (pinfunction "P0.21/RST_3") (pintype "bidirectional"))
    )
    (net (code "33") (name "/RX") (class "Default")
      (node (ref "J2") (pin "9") (pinfunction "9_9") (pintype "passive"))
      (node (ref "TP8") (pin "1") (pinfunction "1_1") (pintype "passive"))
      (node (ref "U1") (pin "69") (pinfunction "PA10_69") (pintype "bidirectional"))
    )
    (net (code "34") (name "/RX BT") (class "Default")
      (node (ref "U1") (pin "55") (pinfunction "PD8_55") (pintype "bidirectional"))
      (node (ref "U5") (pin "11") (pinfunction "RXD(P0.20)_11") (pintype "bidirectional"))
    )
    (net (code "35") (name "/SCL") (class "Default")
      (node (ref "P1") (pin "3") (pinfunction "3_3") (pintype "passive"))
      (node (ref "P2") (pin "3") (pinfunction "3_3") (pintype "passive"))
      (node (ref "P3") (pin "3") (pinfunction "3_3") (pintype "passive"))
      (node (ref "P4") (pin "3") (pinfunction "3_3") (pintype "passive"))
      (node (ref "P5") (pin "3") (pinfunction "3_3") (pintype "passive"))
      (node (ref "R28") (pin "1") (pinfunction "1_1") (pintype "passive"))
      (node (ref "TP9") (pin "1") (pinfunction "1_1") (pintype "passive"))
      (node (ref "U1") (pin "95") (pinfunction "PB8_95") (pintype "bidirectional"))
      (node (ref "U8") (pin "3") (pinfunction "SCL_3") (pintype "input"))
    )
    (net (code "36") (name "/SCLK") (class "Default")
      (node (ref "U1") (pin "52") (pinfunction "PB13_52") (pintype "bidirectional"))
      (node (ref "U2") (pin "13") (pinfunction "AP_SCL/AP_SCLK_13") (pintype "input"))
    )
    (net (code "37") (name "/SDA") (class "Default")
      (node (ref "P1") (pin "4") (pinfunction "4_4") (pintype "passive"))
      (node (ref "P2") (pin "4") (pinfunction "4_4") (pintype "passive"))
      (node (ref "P3") (pin "4") (pinfunction "4_4") (pintype "passive"))
      (node (ref "P4") (pin "4") (pinfunction "4_4") (pintype "passive"))
      (node (ref "P5") (pin "4") (pinfunction "4_4") (pintype "passive"))
      (node (ref "R27") (pin "1") (pinfunction "1_1") (pintype "passive"))
      (node (ref "TP10") (pin "1") (pinfunction "1_1") (pintype "passive"))
      (node (ref "U1") (pin "93") (pinfunction "PB7_93") (pintype "bidirectional"))
      (node (ref "U8") (pin "4") (pinfunction "SDA_4") (pintype "bidirectional"))
    )
    (net (code "38") (name "/SDI") (class "Default")
      (node (ref "U1") (pin "54") (pinfunction "PB15_54") (pintype "bidirectional"))
      (node (ref "U2") (pin "14") (pinfunction "AP_SDA/AP_SDIO/AP_SDI_14") (pintype "bidirectional"))
    )
    (net (code "39") (name "/SDO") (class "Default")
      (node (ref "U1") (pin "53") (pinfunction "PB14_53") (pintype "bidirectional"))
      (node (ref "U2") (pin "1") (pinfunction "AP_SDO/AP_AD0_1") (pintype "bidirectional"))
    )
    (net (code "40") (name "/SWCLK") (class "Default")
      (node (ref "J2") (pin "5") (pinfunction "5_5") (pintype "passive"))
      (node (ref "TP6") (pin "1") (pinfunction "1_1") (pintype "passive"))
      (node (ref "U1") (pin "76") (pinfunction "PA14_76") (pintype "bidirectional"))
    )
    (net (code "41") (name "/SWDIO") (class "Default")
      (node (ref "J2") (pin "3") (pinfunction "3_3") (pintype "passive"))
      (node (ref "TP5") (pin "1") (pinfunction "1_1") (pintype "passive"))
      (node (ref "U1") (pin "72") (pinfunction "PA13_72") (pintype "bidirectional"))
    )
    (net (code "42") (name "/SWITCH") (class "Default")
      (node (ref "S4") (pin "2") (pinfunction "2_2") (pintype "passive"))
      (node (ref "U1") (pin "58") (pinfunction "PD11_58") (pintype "bidirectional"))
    )
    (net (code "43") (name "/SWO") (class "Default")
      (node (ref "J2") (pin "2") (pinfunction "2_2") (pintype "passive"))
      (node (ref "U1") (pin "89") (pinfunction "PB3_89") (pintype "bidirectional"))
    )
    (net (code "44") (name "/TX") (class "Default")
      (node (ref "J2") (pin "7") (pinfunction "7_7") (pintype "passive"))
      (node (ref "TP7") (pin "1") (pinfunction "1_1") (pintype "passive"))
      (node (ref "U1") (pin "68") (pinfunction "PA9_68") (pintype "bidirectional"))
    )
    (net (code "45") (name "/TX BT") (class "Default")
      (node (ref "U1") (pin "56") (pinfunction "PD9_56") (pintype "bidirectional"))
      (node (ref "U5") (pin "12") (pinfunction "TXD(P0.14)_12") (pintype "bidirectional"))
    )
    (net (code "46") (name "/V METER") (class "Default")
      (node (ref "R29") (pin "1") (pinfunction "1_1") (pintype "passive"))
      (node (ref "R30") (pin "2") (pinfunction "2_2") (pintype "passive"))
      (node (ref "U1") (pin "35") (pinfunction "PB1_35") (pintype "bidirectional"))
    )
    (net (code "47") (name "/VCAP1") (class "Default")
      (node (ref "C4") (pin "2") (pinfunction "2_2") (pintype "passive"))
      (node (ref "U1") (pin "48") (pinfunction "VCAP_48") (pintype "power_in"))
    )
    (net (code "48") (name "/VCAP2") (class "Default")
      (node (ref "C5") (pin "2") (pinfunction "2_2") (pintype "passive"))
      (node (ref "U1") (pin "73") (pinfunction "VCAP_73") (pintype "power_in"))
    )
    (net (code "49") (name "/VCP M1") (class "Default")
      (node (ref "C18") (pin "2") (pinfunction "2_2") (pintype "passive"))
      (node (ref "U3") (pin "12") (pinfunction "VCP_12") (pintype "power_in"))
    )
    (net (code "50") (name "/VCP M2") (class "Default")
      (node (ref "C24") (pin "2") (pinfunction "2_2") (pintype "passive"))
      (node (ref "U4") (pin "12") (pinfunction "VCP_12") (pintype "power_in"))
    )
    (net (code "51") (name "/VREF M1") (class "Default")
      (node (ref "C19") (pin "2") (pinfunction "2_2") (pintype "passive"))
      (node (ref "R6") (pin "1") (pinfunction "1_1") (pintype "passive"))
      (node (ref "U3") (pin "5") (pinfunction "VREF_5") (pintype "input"))
    )
    (net (code "52") (name "/VREF M2") (class "Default")
      (node (ref "C20") (pin "2") (pinfunction "2_2") (pintype "passive"))
      (node (ref "R8") (pin "1") (pinfunction "1_1") (pintype "passive"))
      (node (ref "U4") (pin "5") (pinfunction "VREF_5") (pintype "input"))
    )
    (net (code "53") (name "/W{slash}S") (class "Default")
      (node (ref "U1") (pin "63") (pinfunction "PC6_63") (pintype "bidirectional"))
      (node (ref "U5") (pin "7") (pinfunction "WKP(P0.05)_7") (pintype "bidirectional"))
    )
    (net (code "54") (name "/XSHUT1") (class "Default")
      (node (ref "P1") (pin "6") (pinfunction "6_6") (pintype "passive"))
      (node (ref "U1") (pin "97") (pinfunction "PE0_97") (pintype "bidirectional"))
    )
    (net (code "55") (name "/XSHUT2") (class "Default")
      (node (ref "P2") (pin "6") (pinfunction "6_6") (pintype "passive"))
      (node (ref "U1") (pin "98") (pinfunction "PE1_98") (pintype "bidirectional"))
    )
    (net (code "56") (name "/XSHUT3") (class "Default")
      (node (ref "P3") (pin "6") (pinfunction "6_6") (pintype "passive"))
      (node (ref "U1") (pin "1") (pinfunction "PE2_1") (pintype "bidirectional"))
    )
    (net (code "57") (name "/XSHUT4") (class "Default")
      (node (ref "P4") (pin "6") (pinfunction "6_6") (pintype "passive"))
      (node (ref "U1") (pin "3") (pinfunction "PE4_3") (pintype "bidirectional"))
    )
    (net (code "58") (name "/XSHUT5") (class "Default")
      (node (ref "P5") (pin "6") (pinfunction "6_6") (pintype "passive"))
      (node (ref "U1") (pin "4") (pinfunction "PE5_4") (pintype "bidirectional"))
    )
    (net (code "59") (name "3.3V") (class "Default")
      (node (ref "C10") (pin "2") (pinfunction "2_2") (pintype "passive"))
      (node (ref "C11") (pin "1") (pinfunction "1_1") (pintype "passive"))
      (node (ref "C14") (pin "2") (pinfunction "2_2") (pintype "passive"))
      (node (ref "C27") (pin "2") (pinfunction "2_2") (pintype "passive"))
      (node (ref "C29") (pin "2") (pinfunction "2_2") (pintype "passive"))
      (node (ref "C3") (pin "2") (pinfunction "2_2") (pintype "passive"))
      (node (ref "C30") (pin "2") (pinfunction "2_2") (pintype "passive"))
      (node (ref "C6") (pin "2") (pinfunction "2_2") (pintype "passive"))
      (node (ref "C7") (pin "2") (pinfunction "2_2") (pintype "passive"))
      (node (ref "C8") (pin "2") (pinfunction "2_2") (pintype "passive"))
      (node (ref "C9") (pin "2") (pinfunction "2_2") (pintype "passive"))
      (node (ref "FL1") (pin "2") (pinfunction "2_2") (pintype "passive"))
      (node (ref "FL2") (pin "2") (pinfunction "2_2") (pintype "passive"))
      (node (ref "J2") (pin "1") (pinfunction "1_1") (pintype "passive"))
      (node (ref "P1") (pin "1") (pinfunction "1_1") (pintype "passive"))
      (node (ref "P2") (pin "1") (pinfunction "1_1") (pintype "passive"))
      (node (ref "P3") (pin "1") (pinfunction "1_1") (pintype "passive"))
      (node (ref "P4") (pin "1") (pinfunction "1_1") (pintype "passive"))
      (node (ref "P5") (pin "1") (pinfunction "1_1") (pintype "passive"))
      (node (ref "P6") (pin "2") (pinfunction "2_2") (pintype "passive"))
      (node (ref "R10") (pin "1") (pinfunction "1_1") (pintype "passive"))
      (node (ref "R11") (pin "1") (pinfunction "1_1") (pintype "passive"))
      (node (ref "R12") (pin "2") (pinfunction "2_2") (pintype "passive"))
      (node (ref "R13") (pin "1") (pinfunction "1_1") (pintype "passive"))
      (node (ref "R14") (pin "1") (pinfunction "1_1") (pintype "passive"))
      (node (ref "R15") (pin "1") (pinfunction "1_1") (pintype "passive"))
      (node (ref "R17") (pin "2") (pinfunction "2_2") (pintype "passive"))
      (node (ref "R19") (pin "2") (pinfunction "2_2") (pintype "passive"))
      (node (ref "R2") (pin "2") (pinfunction "2_2") (pintype "passive"))
      (node (ref "R21") (pin "2") (pinfunction "2_2") (pintype "passive"))
      (node (ref "R22") (pin "2") (pinfunction "2_2") (pintype "passive"))
      (node (ref "R5") (pin "1") (pinfunction "1_1") (pintype "passive"))
      (node (ref "R7") (pin "1") (pinfunction "1_1") (pintype "passive"))
      (node (ref "S1") (pin "2") (pinfunction "2_2") (pintype "passive"))
      (node (ref "TP1") (pin "1") (pinfunction "1_1") (pintype "passive"))
      (node (ref "U1") (pin "100") (pinfunction "VDD_100") (pintype "power_in"))
      (node (ref "U1") (pin "11") (pinfunction "VDD_11") (pintype "power_in"))
      (node (ref "U1") (pin "27") (pinfunction "VDD_27") (pintype "power_in"))
      (node (ref "U1") (pin "50") (pinfunction "VDD_50") (pintype "power_in"))
      (node (ref "U1") (pin "6") (pinfunction "VBAT_6") (pintype "power_in"))
      (node (ref "U1") (pin "75") (pinfunction "VDD_75") (pintype "power_in"))
      (node (ref "U12") (pin "4") (pinfunction "VOUT_4") (pintype "output"))
      (node (ref "U12") (pin "5") (pinfunction "VOUT_5") (pintype "output"))
      (node (ref "U2") (pin "5") (pinfunction "VDDIO_5") (pintype "power_in"))
      (node (ref "U5") (pin "4") (pinfunction "VCC_4") (pintype "power_in"))
      (node (ref "U8") (pin "2") (pinfunction "VCC_IN_2") (pintype "power_in"))
    )
    (net (code "60") (name "7.4V") (class "Default")
      (node (ref "C13") (pin "2") (pinfunction "2_2") (pintype "passive"))
      (node (ref "C16") (pin "2") (pinfunction "2_2") (pintype "passive"))
      (node (ref "C17") (pin "1") (pinfunction "1_1") (pintype "passive"))
      (node (ref "C22") (pin "2") (pinfunction "2_2") (pintype "passive"))
      (node (ref "C23") (pin "1") (pinfunction "1_1") (pintype "passive"))
      (node (ref "C32") (pin "2") (pinfunction "2_2") (pintype "passive"))
      (node (ref "R29") (pin "2") (pinfunction "2_2") (pintype "passive"))
      (node (ref "TP3") (pin "1") (pinfunction "1_1") (pintype "passive"))
      (node (ref "U12") (pin "1") (pinfunction "EN_1") (pintype "input"))
      (node (ref "U12") (pin "2") (pinfunction "VIN_2") (pintype "input"))
      (node (ref "U3") (pin "11") (pinfunction "VM_11") (pintype "power_in"))
      (node (ref "U4") (pin "11") (pinfunction "VM_11") (pintype "power_in"))
      (node (ref "U9") (pin "3") (pinfunction "D_3") (pintype "passive"))
    )
    (net (code "61") (name "7.4V BAT") (class "Default")
      (node (ref "S2") (pin "1") (pinfunction "COM_1") (pintype "passive"))
      (node (ref "U9") (pin "2") (pinfunction "S_2") (pintype "passive"))
    )
    (net (code "62") (name "BAT") (class "Default")
      (node (ref "J1") (pin "1") (pinfunction "1_1") (pintype "passive"))
      (node (ref "S2") (pin "2") (pinfunction "NO_2") (pintype "passive"))
    )
    (net (code "63") (name "GND") (class "Default")
      (node (ref "C1") (pin "2") (pinfunction "2_2") (pintype "passive"))
      (node (ref "C10") (pin "1") (pinfunction "1_1") (pintype "passive"))
      (node (ref "C11") (pin "2") (pinfunction "2_2") (pintype "passive"))
      (node (ref "C12") (pin "1") (pinfunction "1_1") (pintype "passive"))
      (node (ref "C13") (pin "1") (pinfunction "1_1") (pintype "passive"))
      (node (ref "C14") (pin "1") (pinfunction "1_1") (pintype "passive"))
      (node (ref "C16") (pin "1") (pinfunction "1_1") (pintype "passive"))
      (node (ref "C17") (pin "2") (pinfunction "2_2") (pintype "passive"))
      (node (ref "C19") (pin "1") (pinfunction "1_1") (pintype "passive"))
      (node (ref "C2") (pin "2") (pinfunction "2_2") (pintype "passive"))
      (node (ref "C20") (pin "1") (pinfunction "1_1") (pintype "passive"))
      (node (ref "C22") (pin "1") (pinfunction "1_1") (pintype "passive"))
      (node (ref "C23") (pin "2") (pinfunction "2_2") (pintype "passive"))
      (node (ref "C25") (pin "1") (pinfunction "1_1") (pintype "passive"))
      (node (ref "C26") (pin "1") (pinfunction "1_1") (pintype "passive"))
      (node (ref "C27") (pin "1") (pinfunction "1_1") (pintype "passive"))
      (node (ref "C28") (pin "2") (pinfunction "2_2") (pintype "passive"))
      (node (ref "C29") (pin "1") (pinfunction "1_1") (pintype "passive"))
      (node (ref "C3") (pin "1") (pinfunction "1_1") (pintype "passive"))
      (node (ref "C30") (pin "1") (pinfunction "1_1") (pintype "passive"))
      (node (ref "C31") (pin "1") (pinfunction "1_1") (pintype "passive"))
      (node (ref "C32") (pin "1") (pinfunction "1_1") (pintype "passive"))
      (node (ref "C33") (pin "1") (pinfunction "1_1") (pintype "passive"))
      (node (ref "C34") (pin "1") (pinfunction "1_1") (pintype "passive"))
      (node (ref "C35") (pin "1") (pinfunction "1_1") (pintype "passive"))
      (node (ref "C4") (pin "1") (pinfunction "1_1") (pintype "passive"))
      (node (ref "C5") (pin "1") (pinfunction "1_1") (pintype "passive"))
      (node (ref "C6") (pin "1") (pinfunction "1_1") (pintype "passive"))
      (node (ref "C7") (pin "1") (pinfunction "1_1") (pintype "passive"))
      (node (ref "C8") (pin "1") (pinfunction "1_1") (pintype "passive"))
      (node (ref "C9") (pin "1") (pinfunction "1_1") (pintype "passive"))
      (node (ref "D2") (pin "C") (pinfunction "C_C") (pintype "passive"))
      (node (ref "D3") (pin "C") (pinfunction "C_C") (pintype "passive"))
      (node (ref "D4") (pin "C") (pinfunction "C_C") (pintype "passive"))
      (node (ref "D5") (pin "C") (pinfunction "C_C") (pintype "passive"))
      (node (ref "D6") (pin "C") (pinfunction "C_C") (pintype "passive"))
      (node (ref "D7") (pin "C") (pinfunction "C_C") (pintype "passive"))
      (node (ref "D8") (pin "C") (pinfunction "C_C") (pintype "passive"))
      (node (ref "J1") (pin "2") (pinfunction "2_2") (pintype "passive"))
      (node (ref "J2") (pin "10") (pinfunction "10_10") (pintype "passive"))
      (node (ref "J2") (pin "6") (pinfunction "6_6") (pintype "passive"))
      (node (ref "J2") (pin "8") (pinfunction "8_8") (pintype "passive"))
      (node (ref "P1") (pin "2") (pinfunction "2_2") (pintype "passive"))
      (node (ref "P2") (pin "2") (pinfunction "2_2") (pintype "passive"))
      (node (ref "P3") (pin "2") (pinfunction "2_2") (pintype "passive"))
      (node (ref "P4") (pin "2") (pinfunction "2_2") (pintype "passive"))
      (node (ref "P5") (pin "2") (pinfunction "2_2") (pintype "passive"))
      (node (ref "P6") (pin "1") (pinfunction "1_1") (pintype "passive"))
      (node (ref "Q1") (pin "E") (pinfunction "E_E") (pintype "passive"))
      (node (ref "Q2") (pin "E") (pinfunction "E_E") (pintype "passive"))
      (node (ref "Q3") (pin "E") (pinfunction "E_E") (pintype "passive"))
      (node (ref "R1") (pin "1") (pinfunction "1_1") (pintype "passive"))
      (node (ref "R26") (pin "2") (pinfunction "2_2") (pintype "passive"))
      (node (ref "R3") (pin "1") (pinfunction "1_1") (pintype "passive"))
      (node (ref "R30") (pin "1") (pinfunction "1_1") (pintype "passive"))
      (node (ref "R4") (pin "1") (pinfunction "1_1") (pintype "passive"))
      (node (ref "R9") (pin "1") (pinfunction "1_1") (pintype "passive"))
      (node (ref "S3") (pin "1") (pinfunction "1_1") (pintype "passive"))
      (node (ref "S4") (pin "1") (pinfunction "1_1") (pintype "passive"))
      (node (ref "TP2") (pin "1") (pinfunction "1_1") (pintype "passive"))
      (node (ref "U1") (pin "10") (pinfunction "VSS_10") (pintype "power_in"))
      (node (ref "U1") (pin "19") (pinfunction "VSSA_19") (pintype "power_in"))
      (node (ref "U1") (pin "26") (pinfunction "VSS_26") (pintype "power_in"))
      (node (ref "U1") (pin "49") (pinfunction "VSS_49") (pintype "power_in"))
      (node (ref "U1") (pin "74") (pinfunction "VSS_74") (pintype "power_in"))
      (node (ref "U1") (pin "99") (pinfunction "VSS_99") (pintype "power_in"))
      (node (ref "U12") (pin "10") (pinfunction "GND_10") (pintype "power_in"))
      (node (ref "U12") (pin "11") (pinfunction "GND_11") (pintype "power_in"))
      (node (ref "U12") (pin "12") (pinfunction "GND_12") (pintype "power_in"))
      (node (ref "U12") (pin "3") (pinfunction "GND_3") (pintype "power_in"))
      (node (ref "U12") (pin "9") (pinfunction "GND_9") (pintype "power_in"))
      (node (ref "U2") (pin "10") (pinfunction "RESV_10_10") (pintype "passive"))
      (node (ref "U2") (pin "11") (pinfunction "RESV_11_11") (pintype "passive"))
      (node (ref "U2") (pin "2") (pinfunction "RESV_2_2") (pintype "passive"))
      (node (ref "U2") (pin "3") (pinfunction "RESV_3_3") (pintype "passive"))
      (node (ref "U2") (pin "6") (pinfunction "GND_6") (pintype "power_in"))
      (node (ref "U2") (pin "7") (pinfunction "RESV_7_7") (pintype "passive"))
      (node (ref "U2") (pin "9") (pinfunction "INT2/FSYNC/CLKIN_9") (pintype "bidirectional"))
      (node (ref "U3") (pin "15") (pinfunction "GND_15") (pintype "power_in"))
      (node (ref "U3") (pin "16") (pinfunction "PMODE_16") (pintype "input"))
      (node (ref "U3") (pin "7") (pinfunction "IMODE_7") (pintype "input"))
      (node (ref "U3") (pin "9") (pinfunction "PGND_9") (pintype "power_in"))
      (node (ref "U4") (pin "15") (pinfunction "GND_15") (pintype "power_in"))
      (node (ref "U4") (pin "16") (pinfunction "PMODE_16") (pintype "input"))
      (node (ref "U4") (pin "7") (pinfunction "IMODE_7") (pintype "input"))
      (node (ref "U4") (pin "9") (pinfunction "PGND_9") (pintype "power_in"))
      (node (ref "U5") (pin "14") (pinfunction "GND_14") (pintype "power_in"))
      (node (ref "U5") (pin "5") (pinfunction "GND_5") (pintype "power_in"))
      (node (ref "U6") (pin "2") (pinfunction "C_2") (pintype "passive"))
      (node (ref "U6") (pin "4") (pinfunction "ET_4") (pintype "passive"))
      (node (ref "U7") (pin "2") (pinfunction "C_2") (pintype "passive"))
      (node (ref "U7") (pin "4") (pinfunction "ET_4") (pintype "passive"))
      (node (ref "U8") (pin "1") (pinfunction "GND_1") (pintype "power_in"))
    )
    (net (code "64") (name "Net-(D2-PadA)") (class "Default")
      (node (ref "D2") (pin "A") (pinfunction "A_A") (pintype "passive"))
      (node (ref "R16") (pin "1") (pinfunction "1_1") (pintype "passive"))
    )
    (net (code "65") (name "Net-(D3-PadA)") (class "Default")
      (node (ref "D3") (pin "A") (pinfunction "A_A") (pintype "passive"))
      (node (ref "R18") (pin "1") (pinfunction "1_1") (pintype "passive"))
    )
    (net (code "66") (name "Net-(D4-PadA)") (class "Default")
      (node (ref "D4") (pin "A") (pinfunction "A_A") (pintype "passive"))
      (node (ref "R20") (pin "1") (pinfunction "1_1") (pintype "passive"))
    )
    (net (code "67") (name "Net-(M1-+)") (class "Default")
      (node (ref "M1") (pin "1") (pinfunction "+_1") (pintype "passive"))
      (node (ref "U3") (pin "8") (pinfunction "OUT1_8") (pintype "output"))
    )
    (net (code "68") (name "Net-(M1--)") (class "Default")
      (node (ref "M1") (pin "2") (pinfunction "-_2") (pintype "passive"))
      (node (ref "U3") (pin "10") (pinfunction "OUT2_10") (pintype "output"))
    )
    (net (code "69") (name "Net-(M2-+)") (class "Default")
      (node (ref "M2") (pin "1") (pinfunction "+_1") (pintype "passive"))
      (node (ref "U4") (pin "8") (pinfunction "OUT1_8") (pintype "output"))
    )
    (net (code "70") (name "Net-(M2--)") (class "Default")
      (node (ref "M2") (pin "2") (pinfunction "-_2") (pintype "passive"))
      (node (ref "U4") (pin "10") (pinfunction "OUT2_10") (pintype "output"))
    )
    (net (code "71") (name "Net-(U1-PA0)") (class "Default")
      (node (ref "R31") (pin "1") (pinfunction "1_1") (pintype "passive"))
      (node (ref "U1") (pin "22") (pinfunction "PA0_22") (pintype "bidirectional"))
    )
    (net (code "72") (name "Net-(U1-PA1)") (class "Default")
      (node (ref "R32") (pin "1") (pinfunction "1_1") (pintype "passive"))
      (node (ref "U1") (pin "23") (pinfunction "PA1_23") (pintype "bidirectional"))
    )
    (net (code "73") (name "Net-(U1-PA2)") (class "Default")
      (node (ref "R33") (pin "1") (pinfunction "1_1") (pintype "passive"))
      (node (ref "U1") (pin "24") (pinfunction "PA2_24") (pintype "bidirectional"))
    )
    (net (code "74") (name "Net-(U1-VDDA)") (class "Default")
      (node (ref "C1") (pin "1") (pinfunction "1_1") (pintype "passive"))
      (node (ref "C2") (pin "1") (pinfunction "1_1") (pintype "passive"))
      (node (ref "FL1") (pin "1") (pinfunction "1_1") (pintype "passive"))
      (node (ref "U1") (pin "20") (pinfunction "VREF+_20") (pintype "power_in"))
      (node (ref "U1") (pin "21") (pinfunction "VDDA_21") (pintype "power_in"))
    )
    (net (code "75") (name "Net-(U2-VDD)") (class "Default")
      (node (ref "C25") (pin "2") (pinfunction "2_2") (pintype "passive"))
      (node (ref "C26") (pin "2") (pinfunction "2_2") (pintype "passive"))
      (node (ref "FL2") (pin "1") (pinfunction "1_1") (pintype "passive"))
      (node (ref "U2") (pin "8") (pinfunction "VDD_8") (pintype "power_in"))
    )
    (net (code "76") (name "Net-(U3-CPH)") (class "Default")
      (node (ref "C15") (pin "2") (pinfunction "2_2") (pintype "passive"))
      (node (ref "U3") (pin "13") (pinfunction "CPH_13") (pintype "power_in"))
    )
    (net (code "77") (name "Net-(U3-CPL)") (class "Default")
      (node (ref "C15") (pin "1") (pinfunction "1_1") (pintype "passive"))
      (node (ref "U3") (pin "14") (pinfunction "CPL_14") (pintype "power_in"))
    )
    (net (code "78") (name "Net-(U4-CPH)") (class "Default")
      (node (ref "C21") (pin "2") (pinfunction "2_2") (pintype "passive"))
      (node (ref "U4") (pin "13") (pinfunction "CPH_13") (pintype "power_in"))
    )
    (net (code "79") (name "Net-(U4-CPL)") (class "Default")
      (node (ref "C21") (pin "1") (pinfunction "1_1") (pintype "passive"))
      (node (ref "U4") (pin "14") (pinfunction "CPL_14") (pintype "power_in"))
    )
    (net (code "80") (name "Net-(U5-LINK(P0.16))") (class "Default")
      (node (ref "D1") (pin "C") (pinfunction "C_C") (pintype "passive"))
      (node (ref "U5") (pin "13") (pinfunction "LINK(P0.16)_13") (pintype "bidirectional"))
    )
    (net (code "81") (name "Net-(U6-A)") (class "Default")
      (node (ref "R14") (pin "2") (pinfunction "2_2") (pintype "passive"))
      (node (ref "U6") (pin "1") (pinfunction "A_1") (pintype "passive"))
    )
    (net (code "82") (name "Net-(U7-A)") (class "Default")
      (node (ref "R11") (pin "2") (pinfunction "2_2") (pintype "passive"))
      (node (ref "U7") (pin "1") (pinfunction "A_1") (pintype "passive"))
    )
    (net (code "83") (name "Net-(U9-G)") (class "Default")
      (node (ref "R26") (pin "1") (pinfunction "1_1") (pintype "passive"))
      (node (ref "U9") (pin "1") (pinfunction "G_1") (pintype "passive"))
    )
    (net (code "84") (name "Net-(U12-SS{slash}TR)") (class "Default")
      (node (ref "C12") (pin "2") (pinfunction "2_2") (pintype "passive"))
      (node (ref "U12") (pin "8") (pinfunction "SS/TR_8") (pintype "input"))
    )
    (net (code "85") (name "unconnected-(C18-Pad1)") (class "Default")
      (node (ref "C18") (pin "1") (pinfunction "1_1") (pintype "passive"))
    )
    (net (code "86") (name "unconnected-(C24-Pad1)") (class "Default")
      (node (ref "C24") (pin "1") (pinfunction "1_1") (pintype "passive"))
    )
    (net (code "87") (name "unconnected-(D1-PadA)") (class "Default")
      (node (ref "D1") (pin "A") (pinfunction "A_A") (pintype "passive"))
    )
    (net (code "88") (name "unconnected-(D5-PadA)") (class "Default")
      (node (ref "D5") (pin "A") (pinfunction "A_A") (pintype "passive"))
    )
    (net (code "89") (name "unconnected-(D6-PadA)") (class "Default")
      (node (ref "D6") (pin "A") (pinfunction "A_A") (pintype "passive"))
    )
    (net (code "90") (name "unconnected-(D7-PadA)") (class "Default")
      (node (ref "D7") (pin "A") (pinfunction "A_A") (pintype "passive"))
    )
    (net (code "91") (name "unconnected-(D8-PadA)") (class "Default")
      (node (ref "D8") (pin "A") (pinfunction "A_A") (pintype "passive"))
    )
    (net (code "92") (name "unconnected-(P1-Pad5)") (class "Default")
      (node (ref "P1") (pin "5") (pinfunction "5_5") (pintype "passive+no_connect"))
    )
    (net (code "93") (name "unconnected-(P2-Pad5)") (class "Default")
      (node (ref "P2") (pin "5") (pinfunction "5_5") (pintype "passive+no_connect"))
    )
    (net (code "94") (name "unconnected-(P3-Pad5)") (class "Default")
      (node (ref "P3") (pin "5") (pinfunction "5_5") (pintype "passive+no_connect"))
    )
    (net (code "95") (name "unconnected-(P4-Pad5)") (class "Default")
      (node (ref "P4") (pin "5") (pinfunction "5_5") (pintype "passive+no_connect"))
    )
    (net (code "96") (name "unconnected-(P5-Pad5)") (class "Default")
      (node (ref "P5") (pin "5") (pinfunction "5_5") (pintype "passive+no_connect"))
    )
    (net (code "97") (name "unconnected-(R12-Pad1)") (class "Default")
      (node (ref "R12") (pin "1") (pinfunction "1_1") (pintype "passive"))
    )
    (net (code "98") (name "unconnected-(R22-Pad1)") (class "Default")
      (node (ref "R22") (pin "1") (pinfunction "1_1") (pintype "passive"))
    )
    (net (code "99") (name "unconnected-(R23-Pad1)") (class "Default")
      (node (ref "R23") (pin "1") (pinfunction "1_1") (pintype "passive"))
    )
    (net (code "100") (name "unconnected-(R24-Pad1)") (class "Default")
      (node (ref "R24") (pin "1") (pinfunction "1_1") (pintype "passive"))
    )
    (net (code "101") (name "unconnected-(R25-Pad1)") (class "Default")
      (node (ref "R25") (pin "1") (pinfunction "1_1") (pintype "passive"))
    )
    (net (code "102") (name "unconnected-(U1-PA3-Pad25)") (class "Default")
      (node (ref "U1") (pin "25") (pinfunction "PA3_25") (pintype "bidirectional"))
    )
    (net (code "103") (name "unconnected-(U1-PA6-Pad30)") (class "Default")
      (node (ref "U1") (pin "30") (pinfunction "PA6_30") (pintype "bidirectional"))
    )
    (net (code "104") (name "unconnected-(U1-PA7-Pad31)") (class "Default")
      (node (ref "U1") (pin "31") (pinfunction "PA7_31") (pintype "bidirectional"))
    )
    (net (code "105") (name "unconnected-(U1-PA8-Pad67)") (class "Default")
      (node (ref "U1") (pin "67") (pinfunction "PA8_67") (pintype "bidirectional"))
    )
    (net (code "106") (name "unconnected-(U1-PA11-Pad70)") (class "Default")
      (node (ref "U1") (pin "70") (pinfunction "PA11_70") (pintype "bidirectional"))
    )
    (net (code "107") (name "unconnected-(U1-PA12-Pad71)") (class "Default")
      (node (ref "U1") (pin "71") (pinfunction "PA12_71") (pintype "bidirectional"))
    )
    (net (code "108") (name "unconnected-(U1-PA15-Pad77)") (class "Default")
      (node (ref "U1") (pin "77") (pinfunction "PA15_77") (pintype "bidirectional"))
    )
    (net (code "109") (name "unconnected-(U1-PB0-Pad34)") (class "Default")
      (node (ref "U1") (pin "34") (pinfunction "PB0_34") (pintype "bidirectional"))
    )
    (net (code "110") (name "unconnected-(U1-PB2-Pad36)") (class "Default")
      (node (ref "U1") (pin "36") (pinfunction "PB2_36") (pintype "bidirectional"))
    )
    (net (code "111") (name "unconnected-(U1-PB4-Pad90)") (class "Default")
      (node (ref "U1") (pin "90") (pinfunction "PB4_90") (pintype "bidirectional"))
    )
    (net (code "112") (name "unconnected-(U1-PB5-Pad91)") (class "Default")
      (node (ref "U1") (pin "91") (pinfunction "PB5_91") (pintype "bidirectional"))
    )
    (net (code "113") (name "unconnected-(U1-PB9-Pad96)") (class "Default")
      (node (ref "U1") (pin "96") (pinfunction "PB9_96") (pintype "bidirectional"))
    )
    (net (code "114") (name "unconnected-(U1-PB10-Pad46)") (class "Default")
      (node (ref "U1") (pin "46") (pinfunction "PB10_46") (pintype "bidirectional"))
    )
    (net (code "115") (name "unconnected-(U1-PB11-Pad47)") (class "Default")
      (node (ref "U1") (pin "47") (pinfunction "PB11_47") (pintype "bidirectional"))
    )
    (net (code "116") (name "unconnected-(U1-PB12-Pad51)") (class "Default")
      (node (ref "U1") (pin "51") (pinfunction "PB12_51") (pintype "bidirectional"))
    )
    (net (code "117") (name "unconnected-(U1-PC2_C-Pad17)") (class "Default")
      (node (ref "U1") (pin "17") (pinfunction "PC2_C_17") (pintype "bidirectional"))
    )
    (net (code "118") (name "unconnected-(U1-PC3_C-Pad18)") (class "Default")
      (node (ref "U1") (pin "18") (pinfunction "PC3_C_18") (pintype "bidirectional"))
    )
    (net (code "119") (name "unconnected-(U1-PC10-Pad78)") (class "Default")
      (node (ref "U1") (pin "78") (pinfunction "PC10_78") (pintype "bidirectional"))
    )
    (net (code "120") (name "unconnected-(U1-PC11-Pad79)") (class "Default")
      (node (ref "U1") (pin "79") (pinfunction "PC11_79") (pintype "bidirectional"))
    )
    (net (code "121") (name "unconnected-(U1-PC12-Pad80)") (class "Default")
      (node (ref "U1") (pin "80") (pinfunction "PC12_80") (pintype "bidirectional"))
    )
    (net (code "122") (name "unconnected-(U1-PC13-Pad7)") (class "Default")
      (node (ref "U1") (pin "7") (pinfunction "PC13_7") (pintype "bidirectional"))
    )
    (net (code "123") (name "unconnected-(U1-PC14-OSC32_IN-Pad8)") (class "Default")
      (node (ref "U1") (pin "8") (pinfunction "PC14-OSC32_IN_8") (pintype "bidirectional"))
    )
    (net (code "124") (name "unconnected-(U1-PC15-OSC32_OUT-Pad9)") (class "Default")
      (node (ref "U1") (pin "9") (pinfunction "PC15-OSC32_OUT_9") (pintype "bidirectional"))
    )
    (net (code "125") (name "unconnected-(U1-PD3-Pad84)") (class "Default")
      (node (ref "U1") (pin "84") (pinfunction "PD3_84") (pintype "bidirectional"))
    )
    (net (code "126") (name "unconnected-(U1-PD4-Pad85)") (class "Default")
      (node (ref "U1") (pin "85") (pinfunction "PD4_85") (pintype "bidirectional"))
    )
    (net (code "127") (name "unconnected-(U1-PD5-Pad86)") (class "Default")
      (node (ref "U1") (pin "86") (pinfunction "PD5_86") (pintype "bidirectional"))
    )
    (net (code "128") (name "unconnected-(U1-PD7-Pad88)") (class "Default")
      (node (ref "U1") (pin "88") (pinfunction "PD7_88") (pintype "bidirectional"))
    )
    (net (code "129") (name "unconnected-(U1-PD10-Pad57)") (class "Default")
      (node (ref "U1") (pin "57") (pinfunction "PD10_57") (pintype "bidirectional"))
    )
    (net (code "130") (name "unconnected-(U1-PD15-Pad62)") (class "Default")
      (node (ref "U1") (pin "62") (pinfunction "PD15_62") (pintype "bidirectional"))
    )
    (net (code "131") (name "unconnected-(U1-PE7-Pad37)") (class "Default")
      (node (ref "U1") (pin "37") (pinfunction "PE7_37") (pintype "bidirectional"))
    )
    (net (code "132") (name "unconnected-(U1-PE8-Pad38)") (class "Default")
      (node (ref "U1") (pin "38") (pinfunction "PE8_38") (pintype "bidirectional"))
    )
    (net (code "133") (name "unconnected-(U1-PH0-OSC_IN-Pad12)") (class "Default")
      (node (ref "U1") (pin "12") (pinfunction "PH0-OSC_IN_12") (pintype "bidirectional"))
    )
    (net (code "134") (name "unconnected-(U1-PH1-OSC_OUT-Pad13)") (class "Default")
      (node (ref "U1") (pin "13") (pinfunction "PH1-OSC_OUT_13") (pintype "bidirectional"))
    )
    (net (code "135") (name "unconnected-(U5-P0.00-Pad8)") (class "Default")
      (node (ref "U5") (pin "8") (pinfunction "P0.00_8") (pintype "bidirectional+no_connect"))
    )
    (net (code "136") (name "unconnected-(U5-P0.01-Pad10)") (class "Default")
      (node (ref "U5") (pin "10") (pinfunction "P0.01_10") (pintype "bidirectional+no_connect"))
    )
    (net (code "137") (name "unconnected-(U5-SWCLK-Pad2)") (class "Default")
      (node (ref "U5") (pin "2") (pinfunction "SWCLK_2") (pintype "bidirectional+no_connect"))
    )
    (net (code "138") (name "unconnected-(U5-SWDIO-Pad1)") (class "Default")
      (node (ref "U5") (pin "1") (pinfunction "SWDIO_1") (pintype "bidirectional+no_connect"))
    )
    (net (code "139") (name "unconnected-(U12-PG-Pad7)") (class "Default")
      (node (ref "U12") (pin "7") (pinfunction "PG_7") (pintype "output+no_connect"))
    )
  )
)
